# schematics1.net
KiCad netlist of a schematic drawn in EAGLE
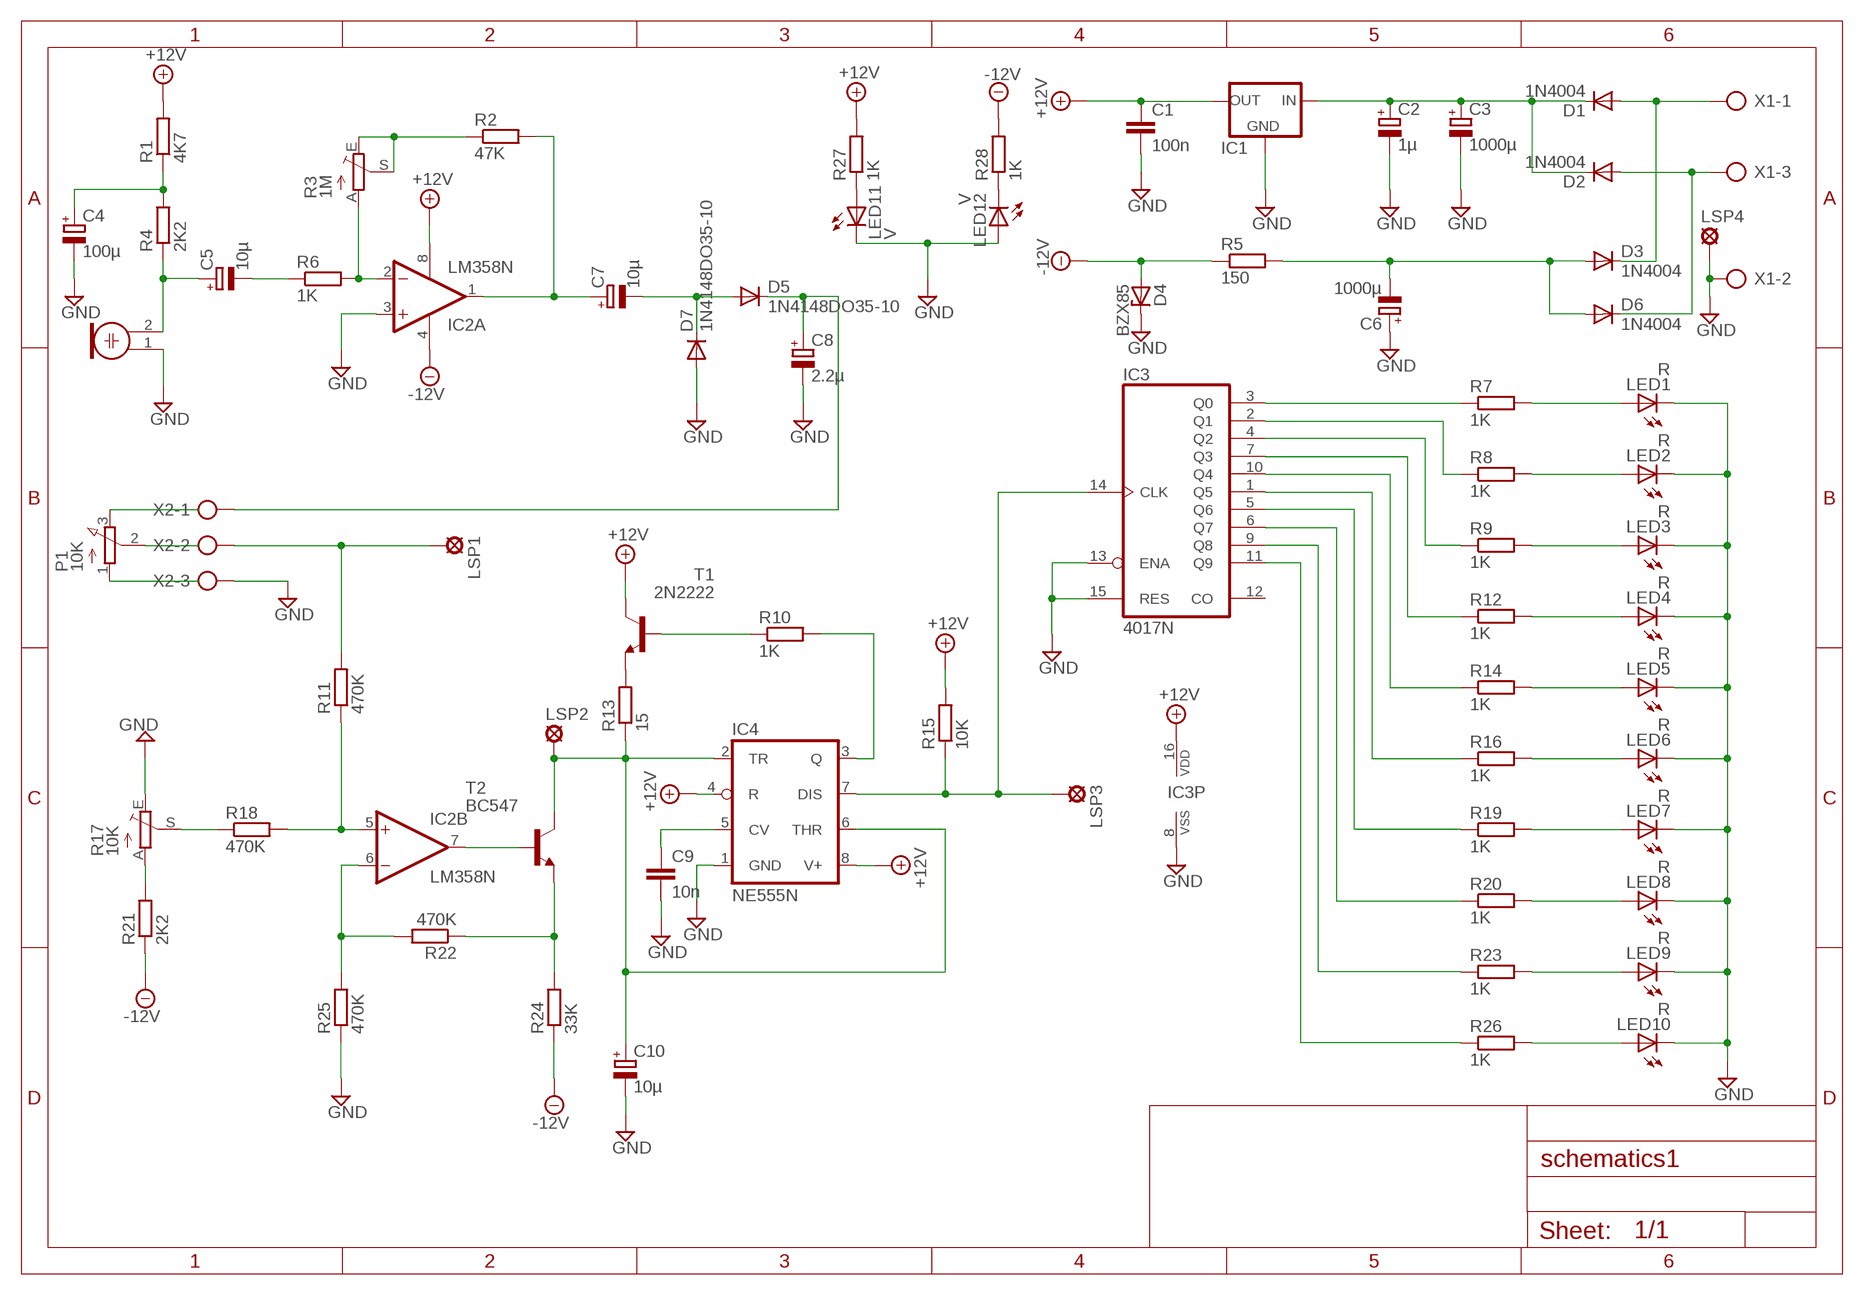
[diagram p0: schematic, sheet 1]

(export (version "E")
  (design (tool "Eeschema 10.0.6"))
  (components
    (comp (ref "C1")
      (value "100n")
      (footprint "eagle-import:C050-035X075")
      (libsource (lib "eagle-import") (part "C-EU050-035X075"))
    )
    (comp (ref "C2")
      (value "1µ")
      (footprint "eagle-import:E2-4")
      (libsource (lib "eagle-import") (part "CPOL-EUE2-4"))
    )
    (comp (ref "C3")
      (value "1000µ")
      (footprint "eagle-import:E5-13")
      (libsource (lib "eagle-import") (part "CPOL-EUE5-13"))
    )
    (comp (ref "C4")
      (value "100µ")
      (footprint "eagle-import:E2,5-6")
      (libsource (lib "eagle-import") (part "CPOL-EUE2.5-6"))
    )
    (comp (ref "C5")
      (value "10µ")
      (footprint "eagle-import:E2-5")
      (libsource (lib "eagle-import") (part "CPOL-EUE2-5"))
    )
    (comp (ref "C6")
      (value "1000µ")
      (footprint "eagle-import:E5-13")
      (libsource (lib "eagle-import") (part "CPOL-EUE5-13"))
    )
    (comp (ref "C7")
      (value "10µ")
      (footprint "eagle-import:E2-5")
      (libsource (lib "eagle-import") (part "CPOL-EUE2-5"))
    )
    (comp (ref "C8")
      (value "2.2µ")
      (footprint "eagle-import:E2-5")
      (libsource (lib "eagle-import") (part "CPOL-EUE2-5"))
    )
    (comp (ref "C9")
      (value "10n")
      (footprint "eagle-import:C050-035X075")
      (libsource (lib "eagle-import") (part "C-EU050-035X075"))
    )
    (comp (ref "C10")
      (value "10µ")
      (footprint "eagle-import:E2-5")
      (libsource (lib "eagle-import") (part "CPOL-EUE2-5"))
    )
    (comp (ref "D1")
      (value "1N4004")
      (footprint "eagle-import:DO41-10")
      (libsource (lib "eagle-import") (part "1N4004"))
    )
    (comp (ref "D2")
      (value "1N4004")
      (footprint "eagle-import:DO41-10")
      (libsource (lib "eagle-import") (part "1N4004"))
    )
    (comp (ref "D3")
      (value "1N4004")
      (footprint "eagle-import:DO41-10")
      (libsource (lib "eagle-import") (part "1N4004"))
    )
    (comp (ref "D4")
      (value "BZX85")
      (footprint "eagle-import:DO41Z10")
      (libsource (lib "eagle-import") (part "BZX85"))
    )
    (comp (ref "D5")
      (value "1N4148DO35-10")
      (footprint "eagle-import:DO35-10")
      (libsource (lib "eagle-import") (part "1N4148DO35-10"))
    )
    (comp (ref "D6")
      (value "1N4004")
      (footprint "eagle-import:DO41-10")
      (libsource (lib "eagle-import") (part "1N4004"))
    )
    (comp (ref "D7")
      (value "1N4148DO35-10")
      (footprint "eagle-import:DO35-10")
      (libsource (lib "eagle-import") (part "1N4148DO35-10"))
    )
    (comp (ref "IC1")
      (value "78XXS")
      (footprint "eagle-import:78XXS")
      (libsource (lib "eagle-import") (part "78XXS"))
    )
    (comp (ref "IC2")
      (value "LM358N")
      (footprint "eagle-import:DIL08")
      (libsource (lib "eagle-import") (part "LM358N"))
    )
    (comp (ref "IC3")
      (value "4017N")
      (footprint "eagle-import:DIL16")
      (libsource (lib "eagle-import") (part "4017N"))
    )
    (comp (ref "IC4")
      (value "NE555N")
      (footprint "eagle-import:DIL08")
      (libsource (lib "eagle-import") (part "555NNE"))
    )
    (comp (ref "LED1")
      (value "R")
      (footprint "eagle-import:LED5MM")
      (libsource (lib "eagle-import") (part "LED5MM"))
    )
    (comp (ref "LED2")
      (value "R")
      (footprint "eagle-import:LED5MM")
      (libsource (lib "eagle-import") (part "LED5MM"))
    )
    (comp (ref "LED3")
      (value "R")
      (footprint "eagle-import:LED5MM")
      (libsource (lib "eagle-import") (part "LED5MM"))
    )
    (comp (ref "LED4")
      (value "R")
      (footprint "eagle-import:LED5MM")
      (libsource (lib "eagle-import") (part "LED5MM"))
    )
    (comp (ref "LED5")
      (value "R")
      (footprint "eagle-import:LED5MM")
      (libsource (lib "eagle-import") (part "LED5MM"))
    )
    (comp (ref "LED6")
      (value "R")
      (footprint "eagle-import:LED5MM")
      (libsource (lib "eagle-import") (part "LED5MM"))
    )
    (comp (ref "LED7")
      (value "R")
      (footprint "eagle-import:LED5MM")
      (libsource (lib "eagle-import") (part "LED5MM"))
    )
    (comp (ref "LED8")
      (value "R")
      (footprint "eagle-import:LED5MM")
      (libsource (lib "eagle-import") (part "LED5MM"))
    )
    (comp (ref "LED9")
      (value "R")
      (footprint "eagle-import:LED5MM")
      (libsource (lib "eagle-import") (part "LED5MM"))
    )
    (comp (ref "LED10")
      (value "R")
      (footprint "eagle-import:LED5MM")
      (libsource (lib "eagle-import") (part "LED5MM"))
    )
    (comp (ref "LED11")
      (value "V")
      (footprint "eagle-import:LED5MM")
      (libsource (lib "eagle-import") (part "LED5MM"))
    )
    (comp (ref "LED12")
      (value "V")
      (footprint "eagle-import:LED5MM")
      (libsource (lib "eagle-import") (part "LED5MM"))
    )
    (comp (ref "LSP1")
      (value "LSP10")
      (footprint "eagle-import:LSP10")
      (libsource (lib "eagle-import") (part "LSP10"))
    )
    (comp (ref "LSP2")
      (value "LSP10")
      (footprint "eagle-import:LSP10")
      (libsource (lib "eagle-import") (part "LSP10"))
    )
    (comp (ref "LSP3")
      (value "LSP10")
      (footprint "eagle-import:LSP10")
      (libsource (lib "eagle-import") (part "LSP10"))
    )
    (comp (ref "LSP4")
      (value "LSP10")
      (footprint "eagle-import:LSP10")
      (libsource (lib "eagle-import") (part "LSP10"))
    )
    (comp (ref "M2")
      (value "ELECTRET_MICROPHON-F6050AP")
      (footprint "eagle-import:F6050AP")
      (libsource (lib "eagle-import") (part "ELECTRET_MICROPHON-F6050AP"))
    )
    (comp (ref "P1")
      (value "10K")
      (footprint "eagle-import:3RP_1610N")
      (libsource (lib "eagle-import") (part "3RP/1610N"))
    )
    (comp (ref "R1")
      (value "4K7")
      (footprint "eagle-import:0207_12")
      (libsource (lib "eagle-import") (part "R-EU_0207/12"))
    )
    (comp (ref "R2")
      (value "47K")
      (footprint "eagle-import:0207_12")
      (libsource (lib "eagle-import") (part "R-EU_0207/12"))
    )
    (comp (ref "R3")
      (value "1M")
      (footprint "eagle-import:CA9V")
      (libsource (lib "eagle-import") (part "TRIM_EU-CA9V"))
    )
    (comp (ref "R4")
      (value "2K2")
      (footprint "eagle-import:0207_12")
      (libsource (lib "eagle-import") (part "R-EU_0207/12"))
    )
    (comp (ref "R5")
      (value "150")
      (footprint "eagle-import:0207_12")
      (libsource (lib "eagle-import") (part "R-EU_0207/12"))
    )
    (comp (ref "R6")
      (value "1K")
      (footprint "eagle-import:0207_12")
      (libsource (lib "eagle-import") (part "R-EU_0207/12"))
    )
    (comp (ref "R7")
      (value "1K")
      (footprint "eagle-import:0207_12")
      (libsource (lib "eagle-import") (part "R-EU_0207/12"))
    )
    (comp (ref "R8")
      (value "1K")
      (footprint "eagle-import:0207_12")
      (libsource (lib "eagle-import") (part "R-EU_0207/12"))
    )
    (comp (ref "R9")
      (value "1K")
      (footprint "eagle-import:0207_12")
      (libsource (lib "eagle-import") (part "R-EU_0207/12"))
    )
    (comp (ref "R10")
      (value "1K")
      (footprint "eagle-import:0207_12")
      (libsource (lib "eagle-import") (part "R-EU_0207/12"))
    )
    (comp (ref "R11")
      (value "470K")
      (footprint "eagle-import:0207_12")
      (libsource (lib "eagle-import") (part "R-EU_0207/12"))
    )
    (comp (ref "R12")
      (value "1K")
      (footprint "eagle-import:0207_12")
      (libsource (lib "eagle-import") (part "R-EU_0207/12"))
    )
    (comp (ref "R13")
      (value "15")
      (footprint "eagle-import:0207_12")
      (libsource (lib "eagle-import") (part "R-EU_0207/12"))
    )
    (comp (ref "R14")
      (value "1K")
      (footprint "eagle-import:0207_12")
      (libsource (lib "eagle-import") (part "R-EU_0207/12"))
    )
    (comp (ref "R15")
      (value "10K")
      (footprint "eagle-import:0207_12")
      (libsource (lib "eagle-import") (part "R-EU_0207/12"))
    )
    (comp (ref "R16")
      (value "1K")
      (footprint "eagle-import:0207_12")
      (libsource (lib "eagle-import") (part "R-EU_0207/12"))
    )
    (comp (ref "R17")
      (value "10K")
      (footprint "eagle-import:CA9V")
      (libsource (lib "eagle-import") (part "TRIM_EU-CA9V"))
    )
    (comp (ref "R18")
      (value "470K")
      (footprint "eagle-import:0207_12")
      (libsource (lib "eagle-import") (part "R-EU_0207/12"))
    )
    (comp (ref "R19")
      (value "1K")
      (footprint "eagle-import:0207_12")
      (libsource (lib "eagle-import") (part "R-EU_0207/12"))
    )
    (comp (ref "R20")
      (value "1K")
      (footprint "eagle-import:0207_12")
      (libsource (lib "eagle-import") (part "R-EU_0207/12"))
    )
    (comp (ref "R21")
      (value "2K2")
      (footprint "eagle-import:0207_12")
      (libsource (lib "eagle-import") (part "R-EU_0207/12"))
    )
    (comp (ref "R22")
      (value "470K")
      (footprint "eagle-import:0207_12")
      (libsource (lib "eagle-import") (part "R-EU_0207/12"))
    )
    (comp (ref "R23")
      (value "1K")
      (footprint "eagle-import:0207_12")
      (libsource (lib "eagle-import") (part "R-EU_0207/12"))
    )
    (comp (ref "R24")
      (value "33K")
      (footprint "eagle-import:0207_12")
      (libsource (lib "eagle-import") (part "R-EU_0207/12"))
    )
    (comp (ref "R25")
      (value "470K")
      (footprint "eagle-import:0207_12")
      (libsource (lib "eagle-import") (part "R-EU_0207/12"))
    )
    (comp (ref "R26")
      (value "1K")
      (footprint "eagle-import:0207_12")
      (libsource (lib "eagle-import") (part "R-EU_0207/12"))
    )
    (comp (ref "R27")
      (value "1K")
      (footprint "eagle-import:0207_12")
      (libsource (lib "eagle-import") (part "R-EU_0207/12"))
    )
    (comp (ref "R28")
      (value "1K")
      (footprint "eagle-import:0207_12")
      (libsource (lib "eagle-import") (part "R-EU_0207/12"))
    )
    (comp (ref "T1")
      (value "2N2222")
      (footprint "eagle-import:TO18")
      (libsource (lib "eagle-import") (part "2N2222"))
    )
    (comp (ref "T2")
      (value "BC547")
      (footprint "eagle-import:TO92")
      (libsource (lib "eagle-import") (part "BC547"))
    )
    (comp (ref "X1")
      (value "AK300/3")
      (footprint "eagle-import:AK300_3")
      (libsource (lib "eagle-import") (part "AK300/3"))
    )
    (comp (ref "X2")
      (value "AK300/3")
      (footprint "eagle-import:AK300_3")
      (libsource (lib "eagle-import") (part "AK300/3"))
    )
  )
  (nets
    (net (code "1") (name "+12V") (class "Default")
      (node (ref "C1") (pin "1") (pinfunction "1_1") (pintype "passive"))
      (node (ref "IC1") (pin "OUT") (pinfunction "OUT_OUT") (pintype "passive"))
      (node (ref "IC2") (pin "8") (pinfunction "V+_8") (pintype "power_in"))
      (node (ref "IC3") (pin "16") (pinfunction "VDD_16") (pintype "power_in"))
      (node (ref "IC4") (pin "4") (pinfunction "R_4") (pintype "input"))
      (node (ref "IC4") (pin "8") (pinfunction "V+_8") (pintype "power_in"))
      (node (ref "R1") (pin "2") (pinfunction "2_2") (pintype "passive"))
      (node (ref "R15") (pin "2") (pinfunction "2_2") (pintype "passive"))
      (node (ref "R27") (pin "2") (pinfunction "2_2") (pintype "passive"))
      (node (ref "T1") (pin "3") (pinfunction "C_3") (pintype "passive"))
    )
    (net (code "2") (name "-12V") (class "Default")
      (node (ref "D4") (pin "A") (pinfunction "A_A") (pintype "passive"))
      (node (ref "IC2") (pin "4") (pinfunction "V-_4") (pintype "power_in"))
      (node (ref "R21") (pin "1") (pinfunction "1_1") (pintype "passive"))
      (node (ref "R24") (pin "1") (pinfunction "1_1") (pintype "passive"))
      (node (ref "R28") (pin "2") (pinfunction "2_2") (pintype "passive"))
      (node (ref "R5") (pin "1") (pinfunction "1_1") (pintype "passive"))
    )
    (net (code "3") (name "GND") (class "Default")
      (node (ref "C1") (pin "2") (pinfunction "2_2") (pintype "passive"))
      (node (ref "C10") (pin "-") (pinfunction "-_-") (pintype "passive"))
      (node (ref "C2") (pin "-") (pinfunction "-_-") (pintype "passive"))
      (node (ref "C3") (pin "-") (pinfunction "-_-") (pintype "passive"))
      (node (ref "C4") (pin "-") (pinfunction "-_-") (pintype "passive"))
      (node (ref "C6") (pin "+") (pinfunction "+_+") (pintype "passive"))
      (node (ref "C8") (pin "-") (pinfunction "-_-") (pintype "passive"))
      (node (ref "C9") (pin "2") (pinfunction "2_2") (pintype "passive"))
      (node (ref "D4") (pin "C") (pinfunction "C_C") (pintype "passive"))
      (node (ref "D7") (pin "A") (pinfunction "A_A") (pintype "passive"))
      (node (ref "IC1") (pin "GND") (pinfunction "GND_GND") (pintype "input"))
      (node (ref "IC2") (pin "3") (pinfunction "+IN_3") (pintype "input"))
      (node (ref "IC3") (pin "13") (pinfunction "ENA_13") (pintype "input"))
      (node (ref "IC3") (pin "15") (pinfunction "RES_15") (pintype "input"))
      (node (ref "IC3") (pin "8") (pinfunction "VSS_8") (pintype "power_in"))
      (node (ref "IC4") (pin "1") (pinfunction "GND_1") (pintype "power_in"))
      (node (ref "LED1") (pin "K") (pinfunction "C_K") (pintype "passive"))
      (node (ref "LED10") (pin "K") (pinfunction "C_K") (pintype "passive"))
      (node (ref "LED11") (pin "K") (pinfunction "C_K") (pintype "passive"))
      (node (ref "LED12") (pin "A") (pinfunction "A_A") (pintype "passive"))
      (node (ref "LED2") (pin "K") (pinfunction "C_K") (pintype "passive"))
      (node (ref "LED3") (pin "K") (pinfunction "C_K") (pintype "passive"))
      (node (ref "LED4") (pin "K") (pinfunction "C_K") (pintype "passive"))
      (node (ref "LED5") (pin "K") (pinfunction "C_K") (pintype "passive"))
      (node (ref "LED6") (pin "K") (pinfunction "C_K") (pintype "passive"))
      (node (ref "LED7") (pin "K") (pinfunction "C_K") (pintype "passive"))
      (node (ref "LED8") (pin "K") (pinfunction "C_K") (pintype "passive"))
      (node (ref "LED9") (pin "K") (pinfunction "C_K") (pintype "passive"))
      (node (ref "LSP4") (pin "MP") (pinfunction "MP_MP") (pintype "passive"))
      (node (ref "M2") (pin "1") (pinfunction "1_1") (pintype "passive"))
      (node (ref "R17") (pin "E") (pinfunction "E_E") (pintype "passive"))
      (node (ref "R25") (pin "1") (pinfunction "1_1") (pintype "passive"))
      (node (ref "X1") (pin "2") (pinfunction "KL_2") (pintype "passive"))
      (node (ref "X2") (pin "3") (pinfunction "KL_3") (pintype "passive"))
    )
    (net (code "4") (name "Net-(C2-Pad+)") (class "Default")
      (node (ref "C2") (pin "+") (pinfunction "+_+") (pintype "passive"))
      (node (ref "C3") (pin "+") (pinfunction "+_+") (pintype "passive"))
      (node (ref "D1") (pin "C") (pinfunction "C_C") (pintype "passive"))
      (node (ref "D2") (pin "C") (pinfunction "C_C") (pintype "passive"))
      (node (ref "IC1") (pin "IN") (pinfunction "IN_IN") (pintype "input"))
    )
    (net (code "5") (name "Net-(C4-Pad+)") (class "Default")
      (node (ref "C4") (pin "+") (pinfunction "+_+") (pintype "passive"))
      (node (ref "R1") (pin "1") (pinfunction "1_1") (pintype "passive"))
      (node (ref "R4") (pin "2") (pinfunction "2_2") (pintype "passive"))
    )
    (net (code "6") (name "Net-(C5-Pad+)") (class "Default")
      (node (ref "C5") (pin "+") (pinfunction "+_+") (pintype "passive"))
      (node (ref "M2") (pin "2") (pinfunction "2_2") (pintype "passive"))
      (node (ref "R4") (pin "1") (pinfunction "1_1") (pintype "passive"))
    )
    (net (code "7") (name "Net-(C5-Pad-)") (class "Default")
      (node (ref "C5") (pin "-") (pinfunction "-_-") (pintype "passive"))
      (node (ref "R6") (pin "1") (pinfunction "1_1") (pintype "passive"))
    )
    (net (code "8") (name "Net-(C6-Pad-)") (class "Default")
      (node (ref "C6") (pin "-") (pinfunction "-_-") (pintype "passive"))
      (node (ref "D3") (pin "A") (pinfunction "A_A") (pintype "passive"))
      (node (ref "D6") (pin "A") (pinfunction "A_A") (pintype "passive"))
      (node (ref "R5") (pin "2") (pinfunction "2_2") (pintype "passive"))
    )
    (net (code "9") (name "Net-(C7-Pad-)") (class "Default")
      (node (ref "C7") (pin "-") (pinfunction "-_-") (pintype "passive"))
      (node (ref "D5") (pin "A") (pinfunction "A_A") (pintype "passive"))
      (node (ref "D7") (pin "C") (pinfunction "C_C") (pintype "passive"))
    )
    (net (code "10") (name "Net-(IC2A--IN)") (class "Default")
      (node (ref "IC2") (pin "2") (pinfunction "-IN_2") (pintype "input"))
      (node (ref "R3") (pin "A") (pinfunction "A_A") (pintype "passive"))
      (node (ref "R6") (pin "2") (pinfunction "2_2") (pintype "passive"))
    )
    (net (code "11") (name "Net-(IC2A-OUT)") (class "Default")
      (node (ref "C7") (pin "+") (pinfunction "+_+") (pintype "passive"))
      (node (ref "IC2") (pin "1") (pinfunction "OUT_1") (pintype "output"))
      (node (ref "R2") (pin "2") (pinfunction "2_2") (pintype "passive"))
    )
    (net (code "12") (name "Net-(IC2B-+IN)") (class "Default")
      (node (ref "IC2") (pin "5") (pinfunction "+IN_5") (pintype "input"))
      (node (ref "R11") (pin "1") (pinfunction "1_1") (pintype "passive"))
      (node (ref "R18") (pin "2") (pinfunction "2_2") (pintype "passive"))
    )
    (net (code "13") (name "Net-(IC2B--IN)") (class "Default")
      (node (ref "IC2") (pin "6") (pinfunction "-IN_6") (pintype "input"))
      (node (ref "R22") (pin "2") (pinfunction "2_2") (pintype "passive"))
      (node (ref "R25") (pin "2") (pinfunction "2_2") (pintype "passive"))
    )
    (net (code "14") (name "Net-(IC2B-OUT)") (class "Default")
      (node (ref "IC2") (pin "7") (pinfunction "OUT_7") (pintype "output"))
      (node (ref "T2") (pin "2") (pinfunction "B_2") (pintype "passive"))
    )
    (net (code "15") (name "Net-(IC3A-CLK)") (class "Default")
      (node (ref "IC3") (pin "14") (pinfunction "CLK_14") (pintype "input"))
      (node (ref "IC4") (pin "7") (pinfunction "DIS_7") (pintype "input"))
      (node (ref "LSP3") (pin "MP") (pinfunction "MP_MP") (pintype "passive"))
      (node (ref "R15") (pin "1") (pinfunction "1_1") (pintype "passive"))
    )
    (net (code "16") (name "Net-(IC3A-Q0)") (class "Default")
      (node (ref "IC3") (pin "3") (pinfunction "Q0_3") (pintype "output"))
      (node (ref "R7") (pin "1") (pinfunction "1_1") (pintype "passive"))
    )
    (net (code "17") (name "Net-(IC3A-Q1)") (class "Default")
      (node (ref "IC3") (pin "2") (pinfunction "Q1_2") (pintype "output"))
      (node (ref "R8") (pin "1") (pinfunction "1_1") (pintype "passive"))
    )
    (net (code "18") (name "Net-(IC3A-Q2)") (class "Default")
      (node (ref "IC3") (pin "4") (pinfunction "Q2_4") (pintype "output"))
      (node (ref "R9") (pin "1") (pinfunction "1_1") (pintype "passive"))
    )
    (net (code "19") (name "Net-(IC3A-Q3)") (class "Default")
      (node (ref "IC3") (pin "7") (pinfunction "Q3_7") (pintype "output"))
      (node (ref "R12") (pin "1") (pinfunction "1_1") (pintype "passive"))
    )
    (net (code "20") (name "Net-(IC3A-Q4)") (class "Default")
      (node (ref "IC3") (pin "10") (pinfunction "Q4_10") (pintype "output"))
      (node (ref "R14") (pin "1") (pinfunction "1_1") (pintype "passive"))
    )
    (net (code "21") (name "Net-(IC3A-Q5)") (class "Default")
      (node (ref "IC3") (pin "1") (pinfunction "Q5_1") (pintype "output"))
      (node (ref "R16") (pin "1") (pinfunction "1_1") (pintype "passive"))
    )
    (net (code "22") (name "Net-(IC3A-Q6)") (class "Default")
      (node (ref "IC3") (pin "5") (pinfunction "Q6_5") (pintype "output"))
      (node (ref "R19") (pin "1") (pinfunction "1_1") (pintype "passive"))
    )
    (net (code "23") (name "Net-(IC3A-Q7)") (class "Default")
      (node (ref "IC3") (pin "6") (pinfunction "Q7_6") (pintype "output"))
      (node (ref "R20") (pin "1") (pinfunction "1_1") (pintype "passive"))
    )
    (net (code "24") (name "Net-(IC3A-Q8)") (class "Default")
      (node (ref "IC3") (pin "9") (pinfunction "Q8_9") (pintype "output"))
      (node (ref "R23") (pin "1") (pinfunction "1_1") (pintype "passive"))
    )
    (net (code "25") (name "Net-(IC3A-Q9)") (class "Default")
      (node (ref "IC3") (pin "11") (pinfunction "Q9_11") (pintype "output"))
      (node (ref "R26") (pin "1") (pinfunction "1_1") (pintype "passive"))
    )
    (net (code "26") (name "Net-(IC4-CV)") (class "Default")
      (node (ref "C9") (pin "1") (pinfunction "1_1") (pintype "passive"))
      (node (ref "IC4") (pin "5") (pinfunction "CV_5") (pintype "input"))
    )
    (net (code "27") (name "Net-(IC4-Q)") (class "Default")
      (node (ref "IC4") (pin "3") (pinfunction "Q_3") (pintype "output"))
      (node (ref "R10") (pin "2") (pinfunction "2_2") (pintype "passive"))
    )
    (net (code "28") (name "Net-(IC4-THR)") (class "Default")
      (node (ref "C10") (pin "+") (pinfunction "+_+") (pintype "passive"))
      (node (ref "IC4") (pin "2") (pinfunction "TR_2") (pintype "input"))
      (node (ref "IC4") (pin "6") (pinfunction "THR_6") (pintype "input"))
      (node (ref "LSP2") (pin "MP") (pinfunction "MP_MP") (pintype "passive"))
      (node (ref "R13") (pin "1") (pinfunction "1_1") (pintype "passive"))
      (node (ref "T2") (pin "3") (pinfunction "C_3") (pintype "passive"))
    )
    (net (code "29") (name "Net-(LED1-PadA)") (class "Default")
      (node (ref "LED1") (pin "A") (pinfunction "A_A") (pintype "passive"))
      (node (ref "R7") (pin "2") (pinfunction "2_2") (pintype "passive"))
    )
    (net (code "30") (name "Net-(LED2-PadA)") (class "Default")
      (node (ref "LED2") (pin "A") (pinfunction "A_A") (pintype "passive"))
      (node (ref "R8") (pin "2") (pinfunction "2_2") (pintype "passive"))
    )
    (net (code "31") (name "Net-(LED3-PadA)") (class "Default")
      (node (ref "LED3") (pin "A") (pinfunction "A_A") (pintype "passive"))
      (node (ref "R9") (pin "2") (pinfunction "2_2") (pintype "passive"))
    )
    (net (code "32") (name "Net-(LED4-PadA)") (class "Default")
      (node (ref "LED4") (pin "A") (pinfunction "A_A") (pintype "passive"))
      (node (ref "R12") (pin "2") (pinfunction "2_2") (pintype "passive"))
    )
    (net (code "33") (name "Net-(LED5-PadA)") (class "Default")
      (node (ref "LED5") (pin "A") (pinfunction "A_A") (pintype "passive"))
      (node (ref "R14") (pin "2") (pinfunction "2_2") (pintype "passive"))
    )
    (net (code "34") (name "Net-(LED6-PadA)") (class "Default")
      (node (ref "LED6") (pin "A") (pinfunction "A_A") (pintype "passive"))
      (node (ref "R16") (pin "2") (pinfunction "2_2") (pintype "passive"))
    )
    (net (code "35") (name "Net-(LED7-PadA)") (class "Default")
      (node (ref "LED7") (pin "A") (pinfunction "A_A") (pintype "passive"))
      (node (ref "R19") (pin "2") (pinfunction "2_2") (pintype "passive"))
    )
    (net (code "36") (name "Net-(LED8-PadA)") (class "Default")
      (node (ref "LED8") (pin "A") (pinfunction "A_A") (pintype "passive"))
      (node (ref "R20") (pin "2") (pinfunction "2_2") (pintype "passive"))
    )
    (net (code "37") (name "Net-(LED9-PadA)") (class "Default")
      (node (ref "LED9") (pin "A") (pinfunction "A_A") (pintype "passive"))
      (node (ref "R23") (pin "2") (pinfunction "2_2") (pintype "passive"))
    )
    (net (code "38") (name "Net-(LED10-PadA)") (class "Default")
      (node (ref "LED10") (pin "A") (pinfunction "A_A") (pintype "passive"))
      (node (ref "R26") (pin "2") (pinfunction "2_2") (pintype "passive"))
    )
    (net (code "39") (name "Net-(LED11-PadA)") (class "Default")
      (node (ref "LED11") (pin "A") (pinfunction "A_A") (pintype "passive"))
      (node (ref "R27") (pin "1") (pinfunction "1_1") (pintype "passive"))
    )
    (net (code "40") (name "Net-(LED12-C)") (class "Default")
      (node (ref "LED12") (pin "K") (pinfunction "C_K") (pintype "passive"))
      (node (ref "R28") (pin "1") (pinfunction "1_1") (pintype "passive"))
    )
    (net (code "41") (name "Net-(R2-Pad1)") (class "Default")
      (node (ref "R2") (pin "1") (pinfunction "1_1") (pintype "passive"))
      (node (ref "R3") (pin "E") (pinfunction "E_E") (pintype "passive"))
      (node (ref "R3") (pin "S") (pinfunction "S_S") (pintype "passive"))
    )
    (net (code "42") (name "Net-(R17-PadA)") (class "Default")
      (node (ref "R17") (pin "A") (pinfunction "A_A") (pintype "passive"))
      (node (ref "R21") (pin "2") (pinfunction "2_2") (pintype "passive"))
    )
    (net (code "43") (name "Net-(R17-PadS)") (class "Default")
      (node (ref "R17") (pin "S") (pinfunction "S_S") (pintype "passive"))
      (node (ref "R18") (pin "1") (pinfunction "1_1") (pintype "passive"))
    )
    (net (code "44") (name "Net-(T1-B)") (class "Default")
      (node (ref "R10") (pin "1") (pinfunction "1_1") (pintype "passive"))
      (node (ref "T1") (pin "2") (pinfunction "B_2") (pintype "passive"))
    )
    (net (code "45") (name "Net-(T1-E)") (class "Default")
      (node (ref "R13") (pin "2") (pinfunction "2_2") (pintype "passive"))
      (node (ref "T1") (pin "1") (pinfunction "E_1") (pintype "passive"))
    )
    (net (code "46") (name "Net-(T2-E)") (class "Default")
      (node (ref "R22") (pin "1") (pinfunction "1_1") (pintype "passive"))
      (node (ref "R24") (pin "2") (pinfunction "2_2") (pintype "passive"))
      (node (ref "T2") (pin "1") (pinfunction "E_1") (pintype "passive"))
    )
    (net (code "47") (name "Net-(X1A-KL)") (class "Default")
      (node (ref "D1") (pin "A") (pinfunction "A_A") (pintype "passive"))
      (node (ref "D3") (pin "C") (pinfunction "C_C") (pintype "passive"))
      (node (ref "X1") (pin "1") (pinfunction "KL_1") (pintype "passive"))
    )
    (net (code "48") (name "Net-(X1C-KL)") (class "Default")
      (node (ref "D2") (pin "A") (pinfunction "A_A") (pintype "passive"))
      (node (ref "D6") (pin "C") (pinfunction "C_C") (pintype "passive"))
      (node (ref "X1") (pin "3") (pinfunction "KL_3") (pintype "passive"))
    )
    (net (code "49") (name "Net-(X2A-KL)") (class "Default")
      (node (ref "C8") (pin "+") (pinfunction "+_+") (pintype "passive"))
      (node (ref "D5") (pin "C") (pinfunction "C_C") (pintype "passive"))
      (node (ref "X2") (pin "1") (pinfunction "KL_1") (pintype "passive"))
    )
    (net (code "50") (name "Net-(X2B-KL)") (class "Default")
      (node (ref "LSP1") (pin "MP") (pinfunction "MP_MP") (pintype "passive"))
      (node (ref "R11") (pin "2") (pinfunction "2_2") (pintype "passive"))
      (node (ref "X2") (pin "2") (pinfunction "KL_2") (pintype "passive"))
    )
    (net (code "51") (name "unconnected-(IC3A-CO-Pad12)") (class "Default")
      (node (ref "IC3") (pin "12") (pinfunction "CO_12") (pintype "output"))
    )
    (net (code "52") (name "unconnected-(P1-A-Pad1)") (class "Default")
      (node (ref "P1") (pin "1") (pinfunction "A_1") (pintype "passive"))
    )
    (net (code "53") (name "unconnected-(P1-E-Pad3)") (class "Default")
      (node (ref "P1") (pin "3") (pinfunction "E_3") (pintype "passive"))
    )
    (net (code "54") (name "unconnected-(P1-S-Pad2)") (class "Default")
      (node (ref "P1") (pin "2") (pinfunction "S_2") (pintype "passive"))
    )
  )
)
